# Eurocard_VME_3U.net
KiCad netlist of a schematic drawn in Altium Designer
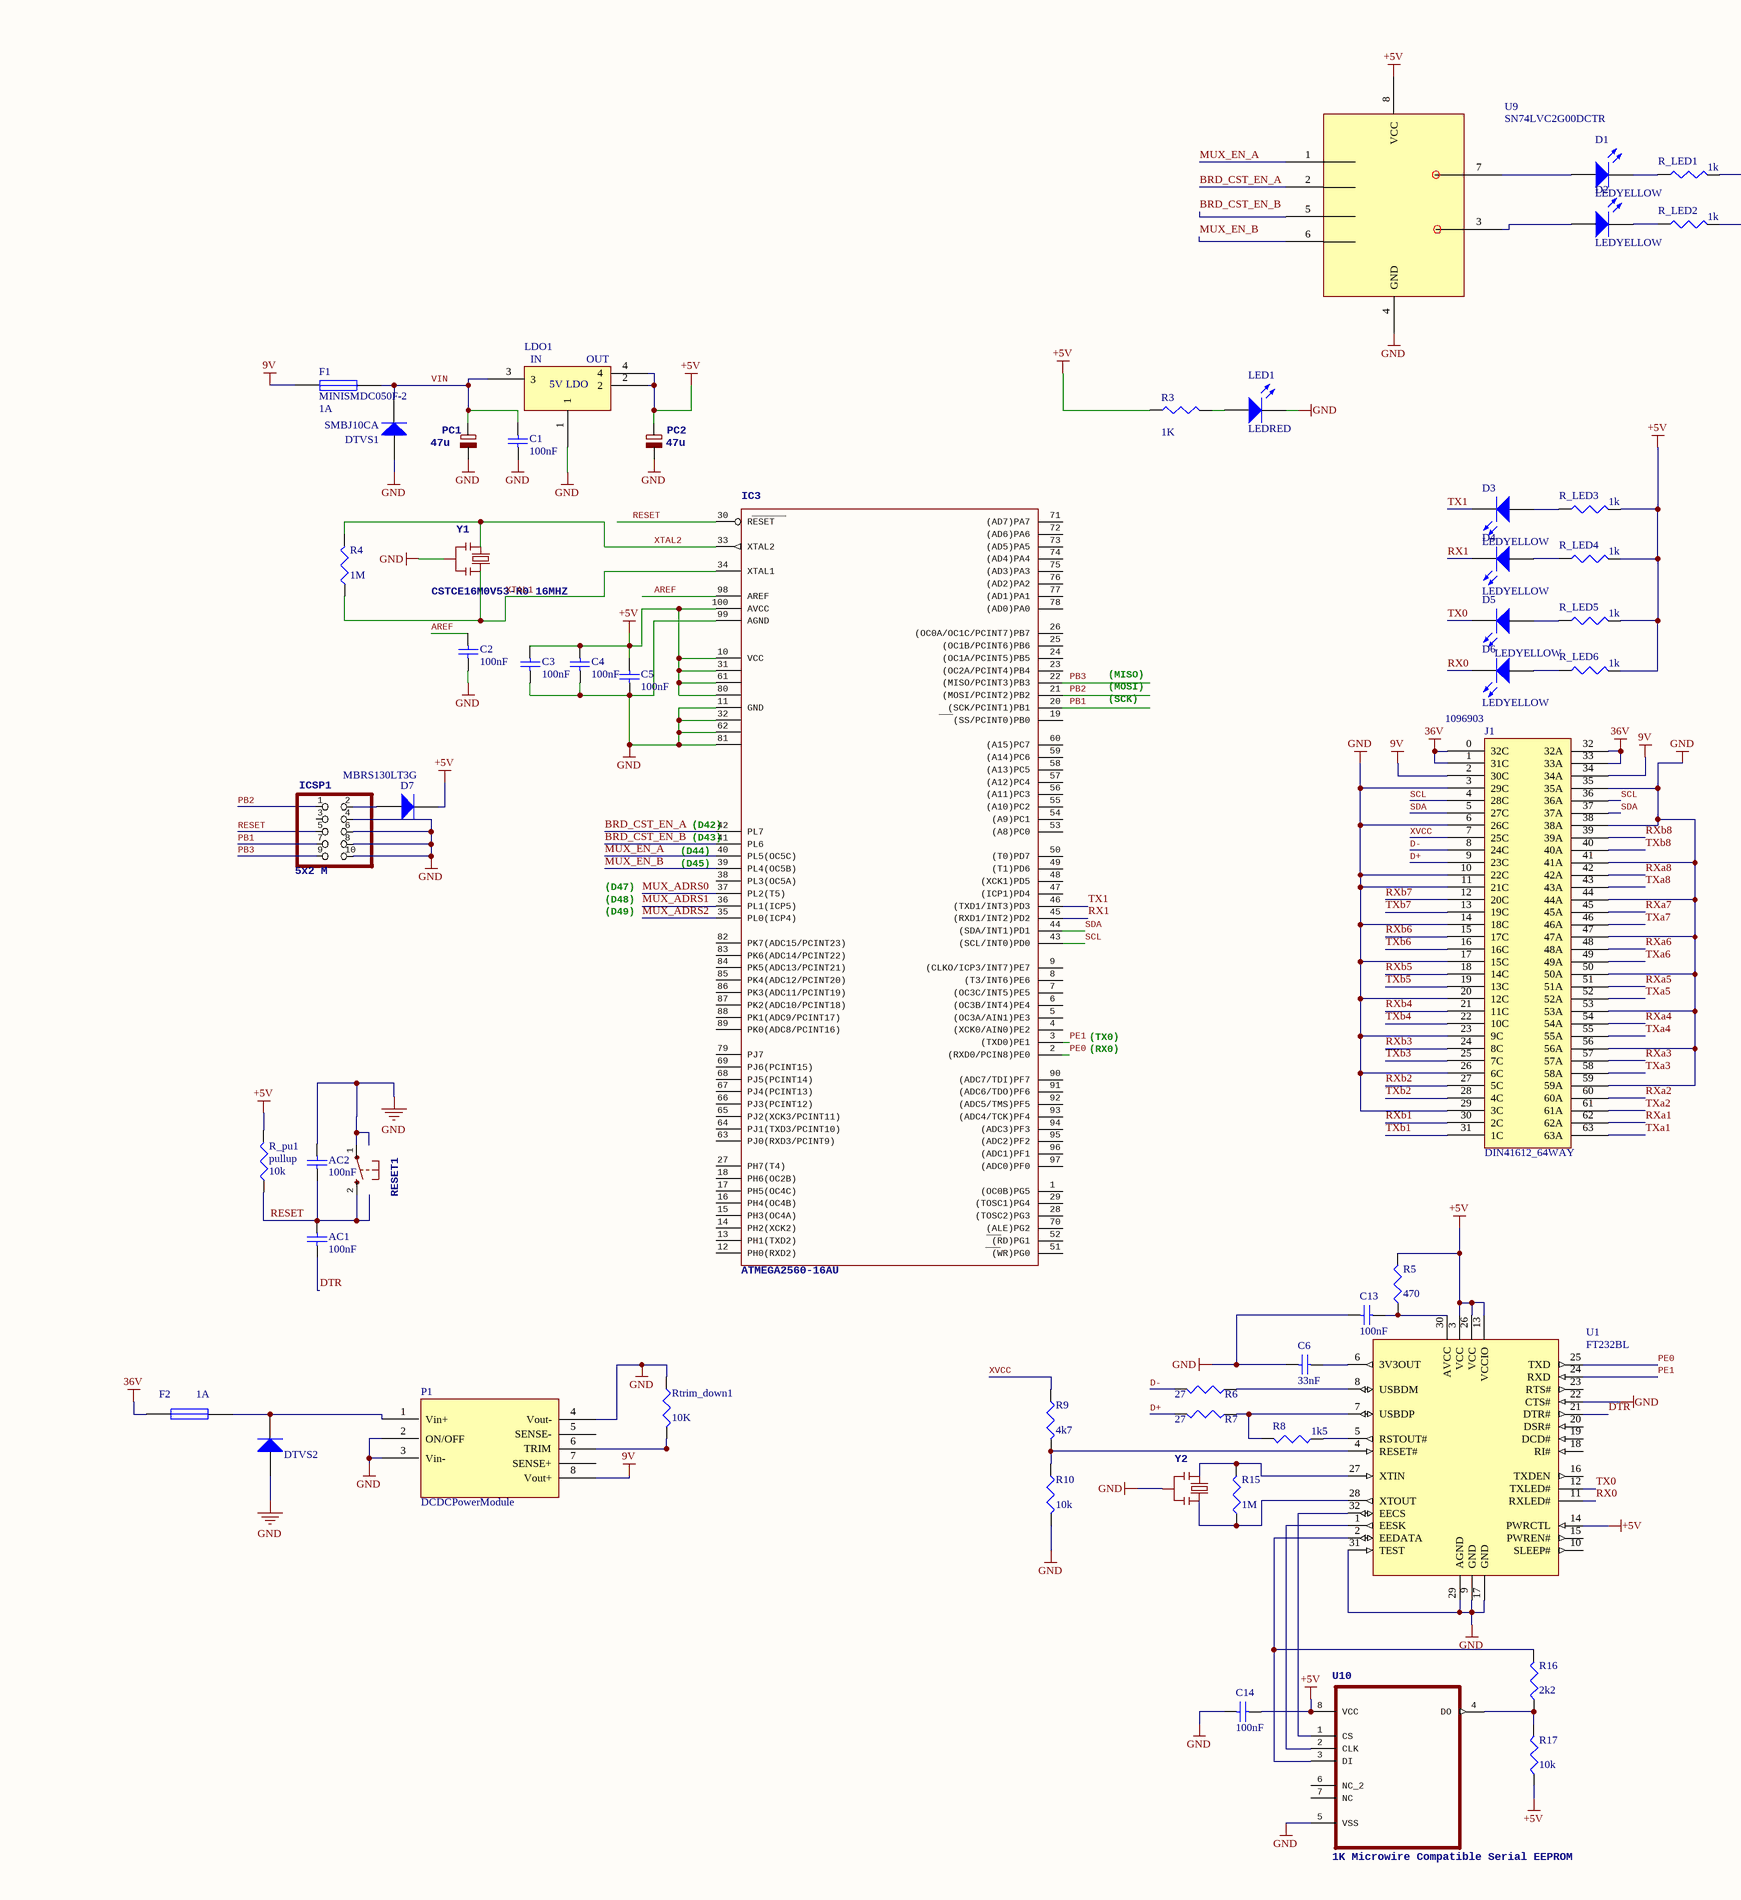
[diagram p0: Eurocard VME 3U (3.937 x 8.660 inches).schdoc, left]
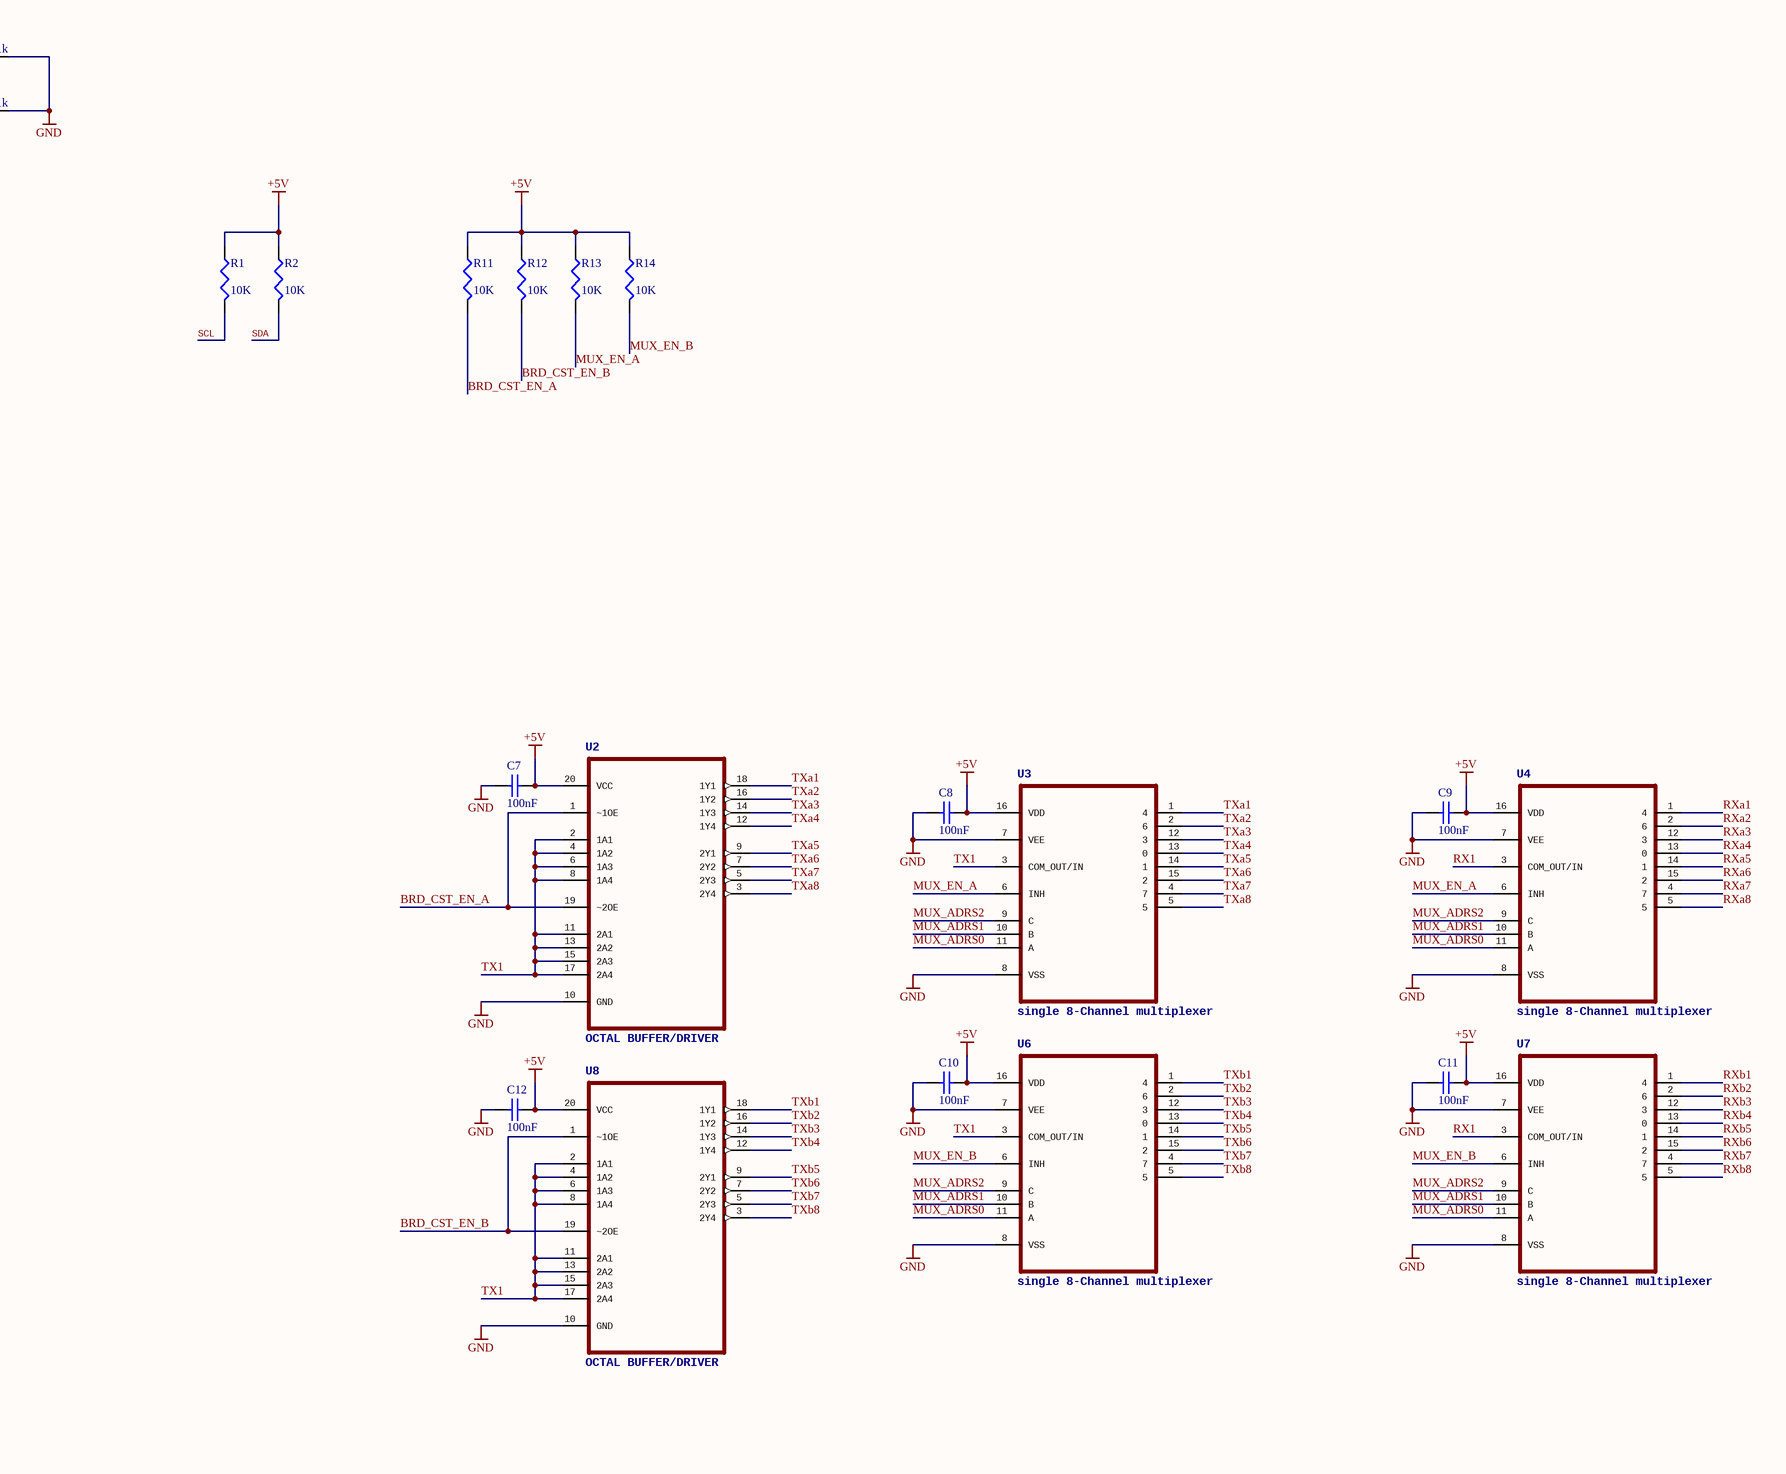
[diagram p1: Eurocard VME 3U (3.937 x 8.660 inches).schdoc, right]

(export (version "E")
  (design (tool "Eeschema 10.0.6"))
  (components
    (comp (ref "AC1")
      (value "100nF")
      (footprint "1608[0603]")
      (description "Capacitor (Semiconductor SIM Model)")
      (fields
        (field (name "PARTNO") "CC0603KRX7R9BB104")
        (field (name "Comment") "Cap Semi")
        (field (name "PUBLISHER") "Altium Limited")
      )
      (libsource (lib "Miscellaneous Devices") (part "Cap Semi"))
    )
    (comp (ref "AC2")
      (value "100nF")
      (footprint "1608[0603]")
      (description "Capacitor (Semiconductor SIM Model)")
      (fields
        (field (name "PARTNO") "CC0603KRX7R9BB104")
        (field (name "Comment") "Cap Semi")
        (field (name "PUBLISHER") "Altium Limited")
      )
      (libsource (lib "Miscellaneous Devices") (part "Cap Semi"))
    )
    (comp (ref "C1")
      (value "100nF")
      (footprint "1608[0603]")
      (description "Capacitor (Semiconductor SIM Model)")
      (fields
        (field (name "PARTNO") "CC0603KRX7R9BB104")
        (field (name "Comment") "Cap Semi")
        (field (name "PUBLISHER") "Altium Limited")
      )
      (libsource (lib "Miscellaneous Devices") (part "Cap Semi"))
    )
    (comp (ref "C2")
      (value "100nF")
      (footprint "1608[0603]")
      (description "Capacitor (Semiconductor SIM Model)")
      (fields
        (field (name "PARTNO") "CC0603KRX7R9BB104")
        (field (name "Comment") "Cap Semi")
        (field (name "PUBLISHER") "Altium Limited")
      )
      (libsource (lib "Miscellaneous Devices") (part "Cap Semi"))
    )
    (comp (ref "C3")
      (value "100nF")
      (footprint "1608[0603]")
      (description "Capacitor (Semiconductor SIM Model)")
      (fields
        (field (name "PARTNO") "CC0603KRX7R9BB104")
        (field (name "Comment") "Cap Semi")
        (field (name "PUBLISHER") "Altium Limited")
      )
      (libsource (lib "Miscellaneous Devices") (part "Cap Semi"))
    )
    (comp (ref "C4")
      (value "100nF")
      (footprint "1608[0603]")
      (description "Capacitor (Semiconductor SIM Model)")
      (fields
        (field (name "PARTNO") "CC0603KRX7R9BB104")
        (field (name "Comment") "Cap Semi")
        (field (name "PUBLISHER") "Altium Limited")
      )
      (libsource (lib "Miscellaneous Devices") (part "Cap Semi"))
    )
    (comp (ref "C5")
      (value "100nF")
      (footprint "1608[0603]")
      (description "Capacitor (Semiconductor SIM Model)")
      (fields
        (field (name "PARTNO") "CC0603KRX7R9BB104")
        (field (name "Comment") "Cap Semi")
        (field (name "PUBLISHER") "Altium Limited")
      )
      (libsource (lib "Miscellaneous Devices") (part "Cap Semi"))
    )
    (comp (ref "C6")
      (value "33nF")
      (footprint "1608[0603]")
      (description "Capacitor (Semiconductor SIM Model)")
      (fields
        (field (name "PARTNO") "0603B332J500CT")
        (field (name "Comment") "Cap Semi")
        (field (name "PUBLISHER") "Altium Limited")
      )
      (libsource (lib "Miscellaneous Devices") (part "Cap Semi"))
    )
    (comp (ref "C7")
      (value "100nF")
      (footprint "1608[0603]")
      (description "Capacitor (Semiconductor SIM Model)")
      (fields (field (name "PARTNO") "CC0603KRX7R9BB104") (field (name "PUBLISHER") "Altium Limited"))
      (libsource (lib "Miscellaneous Devices") (part "Cap Semi"))
    )
    (comp (ref "C8")
      (value "100nF")
      (footprint "1608[0603]")
      (description "Capacitor (Semiconductor SIM Model)")
      (fields (field (name "PARTNO") "CC0603KRX7R9BB104") (field (name "PUBLISHER") "Altium Limited"))
      (libsource (lib "Miscellaneous Devices") (part "Cap Semi"))
    )
    (comp (ref "C9")
      (value "100nF")
      (footprint "1608[0603]")
      (description "Capacitor (Semiconductor SIM Model)")
      (fields (field (name "PARTNO") "CC0603KRX7R9BB104") (field (name "PUBLISHER") "Altium Limited"))
      (libsource (lib "Miscellaneous Devices") (part "Cap Semi"))
    )
    (comp (ref "C10")
      (value "100nF")
      (footprint "1608[0603]")
      (description "Capacitor (Semiconductor SIM Model)")
      (fields (field (name "PARTNO") "CC0603KRX7R9BB104") (field (name "PUBLISHER") "Altium Limited"))
      (libsource (lib "Miscellaneous Devices") (part "Cap Semi"))
    )
    (comp (ref "C11")
      (value "100nF")
      (footprint "1608[0603]")
      (description "Capacitor (Semiconductor SIM Model)")
      (fields (field (name "PARTNO") "CC0603KRX7R9BB104") (field (name "PUBLISHER") "Altium Limited"))
      (libsource (lib "Miscellaneous Devices") (part "Cap Semi"))
    )
    (comp (ref "C12")
      (value "100nF")
      (footprint "1608[0603]")
      (description "Capacitor (Semiconductor SIM Model)")
      (fields (field (name "PARTNO") "CC0603KRX7R9BB104") (field (name "PUBLISHER") "Altium Limited"))
      (libsource (lib "Miscellaneous Devices") (part "Cap Semi"))
    )
    (comp (ref "C13")
      (value "100nF")
      (footprint "1608[0603]")
      (description "Capacitor (Semiconductor SIM Model)")
      (fields
        (field (name "PARTNO") "CC0603KRX7R9BB104")
        (field (name "Comment") "Cap Semi")
        (field (name "PUBLISHER") "Altium Limited")
      )
      (libsource (lib "Miscellaneous Devices") (part "Cap Semi"))
    )
    (comp (ref "C14")
      (value "100nF")
      (footprint "1608[0603]")
      (description "Capacitor (Semiconductor SIM Model)")
      (fields
        (field (name "PARTNO") "CC0603KRX7R9BB104")
        (field (name "Comment") "Cap Semi")
        (field (name "PUBLISHER") "Altium Limited")
      )
      (libsource (lib "Miscellaneous Devices") (part "Cap Semi"))
    )
    (comp (ref "D1")
      (value "LEDYELLOW")
      (footprint "LEDYELLOW")
      (fields (field (name "PARTNO") "550-0307F"))
      (libsource (lib "G2_LV") (part "LEDYELLOW"))
    )
    (comp (ref "D2")
      (value "LEDYELLOW")
      (footprint "LEDYELLOW")
      (fields (field (name "PARTNO") "550-0307F"))
      (libsource (lib "G2_LV") (part "LEDYELLOW"))
    )
    (comp (ref "D3")
      (value "LEDYELLOW")
      (footprint "LEDYELLOW")
      (fields (field (name "PARTNO") "550-0307F"))
      (libsource (lib "G2_LV") (part "LEDYELLOW"))
    )
    (comp (ref "D4")
      (value "LEDYELLOW")
      (footprint "LEDYELLOW")
      (fields (field (name "PARTNO") "550-0307F"))
      (libsource (lib "G2_LV") (part "LEDYELLOW"))
    )
    (comp (ref "D5")
      (value "LEDYELLOW")
      (footprint "LEDYELLOW")
      (fields (field (name "PARTNO") "550-0307F"))
      (libsource (lib "G2_LV") (part "LEDYELLOW"))
    )
    (comp (ref "D6")
      (value "LEDYELLOW")
      (footprint "LEDYELLOW")
      (fields (field (name "PARTNO") "550-0307F"))
      (libsource (lib "G2_LV") (part "LEDYELLOW"))
    )
    (comp (ref "D7")
      (value "MBRS130LT3G")
      (footprint "SMB-403A")
      (description "Power Diode")
      (fields (field (name "PUBLISHER") "Altium Limited"))
      (libsource (lib "G2_LV") (part "MBRS130LT3G"))
    )
    (comp (ref "DTVS1")
      (value "SMBJ10CA")
      (footprint "DO-214AA")
      (description "TVS")
      (fields (field (name "PUBLISHER") "Altium Limited"))
      (libsource (lib "G2_LV") (part "SMBJ"))
    )
    (comp (ref "DTVS2")
      (value "SMBJ48A")
      (footprint "SMBJ")
      (description "TVS")
      (fields (field (name "PARTNO") "SMBJ36A") (field (name "PUBLISHER") "Altium Limited"))
      (libsource (lib "G2_LV") (part "SMBJ"))
    )
    (comp (ref "F1")
      (value "MINISMDC050F-2")
      (footprint "MF-MSMF1")
      (description "Fuse")
      (fields (field (name "TRIPPING CURRENT") "1A") (field (name "PUBLISHER") "Altium Limited"))
      (libsource (lib "G2_LV") (part "Fuse 1"))
    )
    (comp (ref "F2")
      (value "~")
      (footprint "LV1:MC33192")
      (description "Fuse")
      (fields
        (field (name "TRIPPING CURRENT") "1A")
        (field (name "PARTNO") "MC33192")
        (field (name "PUBLISHER") "Altium Limited")
      )
      (libsource (lib "G2_LV") (part "Fuse 1"))
    )
    (comp (ref "IC3")
      (value "ATMEGA2560-16AU")
      (footprint "LV1:100A_N")
      (libsource (lib "SmartPrj") (part "ATMEGA2560AU"))
    )
    (comp (ref "ICSP1")
      (value "5x2 M")
      (footprint "2X05")
      (fields (field (name "PARTNO") "2-1761605-3"))
      (libsource (lib "G2_LV") (part "PINHD-2X5"))
    )
    (comp (ref "J1")
      (value "DIN41612_64WAY")
      (footprint "09 03 164 6919")
      (fields (field (name "PARTNO") "0903 164 6921") (field (name "SUPPLIER PART NUMBER 1") "1096903"))
      (libsource (lib "G2_LV") (part "DIN41612_64WAY"))
    )
    (comp (ref "LDO1")
      (value "LDO_5V")
      (footprint "SOT223")
      (fields (field (name "PARTNO") "NCP1117ST50T3G"))
      (libsource (lib "G2_LV") (part "LDO_5V"))
    )
    (comp (ref "LED1")
      (value "LEDRED")
      (footprint "LEDRED")
      (fields (field (name "PARTNO") "550-0407F"))
      (libsource (lib "G2_LV") (part "LEDRED"))
    )
    (comp (ref "P1")
      (value "DCDCPowerModule")
      (footprint "EHHD006A0B41-HZ")
      (fields (field (name "PARTNO") "EHHD006A0B41-HZ"))
      (libsource (lib "G2_LV") (part "DCDCPowerModule"))
    )
    (comp (ref "PC1")
      (value "47u")
      (footprint "PANASONIC_D")
      (description "POLARIZED CAPACITOR, European symbol")
      (fields (field (name "PARTNO") "EEE1EA470WAP"))
      (libsource (lib "rcl") (part "CPOL-EUD"))
    )
    (comp (ref "PC2")
      (value "47u")
      (footprint "PANASONIC_D")
      (description "POLARIZED CAPACITOR, European symbol")
      (fields (field (name "PARTNO") "EEE1EA470WAP"))
      (libsource (lib "rcl") (part "CPOL-EUD"))
    )
    (comp (ref "R1")
      (value "10K")
      (footprint "J1-0603")
      (description "Resistor")
      (fields (field (name "PUBLISHER") "Altium Limited"))
      (libsource (lib "Miscellaneous Devices") (part "Res3"))
    )
    (comp (ref "R2")
      (value "10K")
      (footprint "J1-0603")
      (description "Resistor")
      (fields (field (name "PUBLISHER") "Altium Limited"))
      (libsource (lib "Miscellaneous Devices") (part "Res3"))
    )
    (comp (ref "R3")
      (value "1K")
      (footprint "J1-0603")
      (description "Resistor")
      (fields (field (name "PUBLISHER") "Altium Limited"))
      (libsource (lib "Miscellaneous Devices") (part "Res3"))
    )
    (comp (ref "R4")
      (value "1M")
      (footprint "J1-0603")
      (description "Resistor")
      (fields (field (name "PUBLISHER") "Altium Limited"))
      (libsource (lib "Miscellaneous Devices") (part "Res3"))
    )
    (comp (ref "R5")
      (value "470")
      (footprint "J1-0603")
      (description "Resistor")
      (fields (field (name "PUBLISHER") "Altium Limited"))
      (libsource (lib "Miscellaneous Devices") (part "Res3"))
    )
    (comp (ref "R6")
      (value "27")
      (footprint "J1-0603")
      (description "Resistor")
      (fields (field (name "PUBLISHER") "Altium Limited"))
      (libsource (lib "Miscellaneous Devices") (part "Res3"))
    )
    (comp (ref "R7")
      (value "27")
      (footprint "J1-0603")
      (description "Resistor")
      (fields (field (name "PUBLISHER") "Altium Limited"))
      (libsource (lib "Miscellaneous Devices") (part "Res3"))
    )
    (comp (ref "R8")
      (value "1k5")
      (footprint "J1-0603")
      (description "Resistor")
      (fields (field (name "PUBLISHER") "Altium Limited"))
      (libsource (lib "Miscellaneous Devices") (part "Res3"))
    )
    (comp (ref "R9")
      (value "4k7")
      (footprint "J1-0603")
      (description "Resistor")
      (fields (field (name "PUBLISHER") "Altium Limited"))
      (libsource (lib "Miscellaneous Devices") (part "Res3"))
    )
    (comp (ref "R10")
      (value "10k")
      (footprint "J1-0603")
      (description "Resistor")
      (fields (field (name "PUBLISHER") "Altium Limited"))
      (libsource (lib "Miscellaneous Devices") (part "Res3"))
    )
    (comp (ref "R11")
      (value "10K")
      (footprint "J1-0603")
      (description "Resistor")
      (fields (field (name "PUBLISHER") "Altium Limited"))
      (libsource (lib "Miscellaneous Devices") (part "Res3"))
    )
    (comp (ref "R12")
      (value "10K")
      (footprint "J1-0603")
      (description "Resistor")
      (fields (field (name "PUBLISHER") "Altium Limited"))
      (libsource (lib "Miscellaneous Devices") (part "Res3"))
    )
    (comp (ref "R13")
      (value "10K")
      (footprint "J1-0603")
      (description "Resistor")
      (fields (field (name "PUBLISHER") "Altium Limited"))
      (libsource (lib "Miscellaneous Devices") (part "Res3"))
    )
    (comp (ref "R14")
      (value "10K")
      (footprint "J1-0603")
      (description "Resistor")
      (fields (field (name "PUBLISHER") "Altium Limited"))
      (libsource (lib "Miscellaneous Devices") (part "Res3"))
    )
    (comp (ref "R15")
      (value "1M")
      (footprint "J1-0603")
      (description "Resistor")
      (fields (field (name "PUBLISHER") "Altium Limited"))
      (libsource (lib "Miscellaneous Devices") (part "Res3"))
    )
    (comp (ref "R16")
      (value "2k2")
      (footprint "J1-0603")
      (description "Resistor")
      (fields (field (name "PUBLISHER") "Altium Limited"))
      (libsource (lib "Miscellaneous Devices") (part "Res3"))
    )
    (comp (ref "R17")
      (value "10k")
      (footprint "J1-0603")
      (description "Resistor")
      (fields (field (name "PUBLISHER") "Altium Limited"))
      (libsource (lib "Miscellaneous Devices") (part "Res3"))
    )
    (comp (ref "RESET1")
      (value "PB_RST")
      (footprint "1-1825027-4")
      (fields (field (name "PARTNO") "1-1825027-4"))
      (libsource (lib "G2_LV") (part "PB_RST"))
    )
    (comp (ref "Rtrim_down1")
      (value "10K")
      (footprint "J1-0603")
      (description "Resistor")
      (fields (field (name "PUBLISHER") "Altium Limited"))
      (libsource (lib "Miscellaneous Devices") (part "Res3"))
    )
    (comp (ref "R_LED1")
      (value "1k")
      (footprint "J1-0603")
      (description "Resistor")
      (fields (field (name "Comment") "Res3") (field (name "PUBLISHER") "Altium Limited"))
      (libsource (lib "Miscellaneous Devices") (part "Res3"))
    )
    (comp (ref "R_LED2")
      (value "1k")
      (footprint "J1-0603")
      (description "Resistor")
      (fields (field (name "Comment") "Res3") (field (name "PUBLISHER") "Altium Limited"))
      (libsource (lib "Miscellaneous Devices") (part "Res3"))
    )
    (comp (ref "R_LED3")
      (value "1k")
      (footprint "J1-0603")
      (description "Resistor")
      (fields (field (name "Comment") "Res3") (field (name "PUBLISHER") "Altium Limited"))
      (libsource (lib "Miscellaneous Devices") (part "Res3"))
    )
    (comp (ref "R_LED4")
      (value "1k")
      (footprint "J1-0603")
      (description "Resistor")
      (fields (field (name "Comment") "Res3") (field (name "PUBLISHER") "Altium Limited"))
      (libsource (lib "Miscellaneous Devices") (part "Res3"))
    )
    (comp (ref "R_LED5")
      (value "1k")
      (footprint "J1-0603")
      (description "Resistor")
      (fields (field (name "Comment") "Res3") (field (name "PUBLISHER") "Altium Limited"))
      (libsource (lib "Miscellaneous Devices") (part "Res3"))
    )
    (comp (ref "R_LED6")
      (value "1k")
      (footprint "J1-0603")
      (description "Resistor")
      (fields (field (name "Comment") "Res3") (field (name "PUBLISHER") "Altium Limited"))
      (libsource (lib "Miscellaneous Devices") (part "Res3"))
    )
    (comp (ref "R_pu1")
      (value "pullup")
      (footprint "J1-0603")
      (description "Resistor")
      (fields (field (name "ALTIUM_VALUE") "10k") (field (name "PUBLISHER") "Altium Limited"))
      (libsource (lib "Miscellaneous Devices") (part "Res3"))
    )
    (comp (ref "U1")
      (value "FT232BL")
      (footprint "LQFP-32_N")
      (description "USB UART Asynchronous Serial Data Transfer Chip, 0 to +70 degC, 32-pin LQFP, Pb-Free")
      (fields (field (name "MANUFACTURER") "FTDI"))
      (libsource (lib "FTDI FT Series") (part "FT232BL"))
    )
    (comp (ref "U2")
      (value "OCTAL BUFFER/DRIVER")
      (footprint "SOP65P640X120-20N")
      (fields (field (name "PARTNO") "SN74LVC244APWR"))
      (libsource (lib "G2_LV") (part "SN74LVC244APWR"))
    )
    (comp (ref "U3")
      (value "single 8-Channel multiplexer")
      (footprint "SOP65P640X120-16N")
      (fields (field (name "PARTNO") "CD4051BPW"))
      (libsource (lib "G2_LV") (part "CD4051BPW"))
    )
    (comp (ref "U4")
      (value "single 8-Channel multiplexer")
      (footprint "SOP65P640X120-16N")
      (fields (field (name "PARTNO") "CD4051BPW"))
      (libsource (lib "G2_LV") (part "CD4051BPW"))
    )
    (comp (ref "U6")
      (value "single 8-Channel multiplexer")
      (footprint "SOP65P640X120-16N")
      (fields (field (name "PARTNO") "CD4051BPW"))
      (libsource (lib "G2_LV") (part "CD4051BPW"))
    )
    (comp (ref "U7")
      (value "single 8-Channel multiplexer")
      (footprint "SOP65P640X120-16N")
      (fields (field (name "PARTNO") "CD4051BPW"))
      (libsource (lib "G2_LV") (part "CD4051BPW"))
    )
    (comp (ref "U8")
      (value "OCTAL BUFFER/DRIVER")
      (footprint "SOP65P640X120-20N")
      (fields (field (name "PARTNO") "SN74LVC244APWR"))
      (libsource (lib "G2_LV") (part "SN74LVC244APWR"))
    )
    (comp (ref "U9")
      (value "SN74LVC2G00DCTR")
      (footprint "SOP8")
      (libsource (lib "G2_LV") (part "SN74LVC2G00DCTR"))
    )
    (comp (ref "U10")
      (value "1K Microwire Compatible Serial EEPROM")
      (footprint "SOIC127P600X175-8N")
      (fields (field (name "PARTNO") "93LC46B-I/SN"))
      (libsource (lib "G2_LV") (part "93LC46B-I/SN"))
    )
    (comp (ref "Y1")
      (value "CSTCE16M0V53-R0 16MHZ")
      (footprint "RESONATOR")
      (fields (field (name "PARTNO") "CSTCE16M0V53-R0"))
      (libsource (lib "SmartPrj") (part "RESONATORMU"))
    )
    (comp (ref "Y2")
      (value "~")
      (footprint "CSTCR6M00G53-R0")
      (fields (field (name "PARTNO") "CSTCR6M00G53-R0"))
      (libsource (lib "SmartPrj") (part "RESONATORMU"))
    )
  )
  (nets
    (net (code "1") (name "+5V") (class "Default")
      (node (ref "C10") (pin "1") (pinfunction "1_1") (pintype "passive"))
      (node (ref "C11") (pin "1") (pinfunction "1_1") (pintype "passive"))
      (node (ref "C12") (pin "1") (pinfunction "1_1") (pintype "passive"))
      (node (ref "C14") (pin "1") (pinfunction "1_1") (pintype "passive"))
      (node (ref "C3") (pin "2") (pinfunction "2_2") (pintype "passive"))
      (node (ref "C4") (pin "2") (pinfunction "2_2") (pintype "passive"))
      (node (ref "C5") (pin "2") (pinfunction "2_2") (pintype "passive"))
      (node (ref "C7") (pin "1") (pinfunction "1_1") (pintype "passive"))
      (node (ref "C8") (pin "1") (pinfunction "1_1") (pintype "passive"))
      (node (ref "C9") (pin "1") (pinfunction "1_1") (pintype "passive"))
      (node (ref "D7") (pin "1") (pinfunction "K_1") (pintype "passive"))
      (node (ref "IC3") (pin "10") (pinfunction "VCC_10") (pintype "power_in"))
      (node (ref "IC3") (pin "100") (pinfunction "AVCC_100") (pintype "power_in"))
      (node (ref "IC3") (pin "31") (pinfunction "VCC1_31") (pintype "power_in"))
      (node (ref "IC3") (pin "61") (pinfunction "VCC2_61") (pintype "power_in"))
      (node (ref "IC3") (pin "80") (pinfunction "VCC3_80") (pintype "power_in"))
      (node (ref "LDO1") (pin "2") (pinfunction "2_2") (pintype "passive"))
      (node (ref "LDO1") (pin "4") (pinfunction "4_4") (pintype "passive"))
      (node (ref "PC2") (pin "+") (pinfunction "+_+") (pintype "passive"))
      (node (ref "R1") (pin "1") (pinfunction "1_1") (pintype "passive"))
      (node (ref "R11") (pin "1") (pinfunction "1_1") (pintype "passive"))
      (node (ref "R12") (pin "1") (pinfunction "1_1") (pintype "passive"))
      (node (ref "R13") (pin "1") (pinfunction "1_1") (pintype "passive"))
      (node (ref "R14") (pin "1") (pinfunction "1_1") (pintype "passive"))
      (node (ref "R17") (pin "1") (pinfunction "1_1") (pintype "passive"))
      (node (ref "R2") (pin "1") (pinfunction "1_1") (pintype "passive"))
      (node (ref "R3") (pin "1") (pinfunction "1_1") (pintype "passive"))
      (node (ref "R5") (pin "2") (pinfunction "2_2") (pintype "passive"))
      (node (ref "R_LED3") (pin "2") (pinfunction "2_2") (pintype "passive"))
      (node (ref "R_LED4") (pin "2") (pinfunction "2_2") (pintype "passive"))
      (node (ref "R_LED5") (pin "2") (pinfunction "2_2") (pintype "passive"))
      (node (ref "R_LED6") (pin "2") (pinfunction "2_2") (pintype "passive"))
      (node (ref "R_pu1") (pin "2") (pinfunction "2_2") (pintype "passive"))
      (node (ref "U1") (pin "13") (pinfunction "VCCIO_13") (pintype "power_in"))
      (node (ref "U1") (pin "14") (pinfunction "PWRCTL_14") (pintype "input"))
      (node (ref "U1") (pin "26") (pinfunction "VCC_26") (pintype "power_in"))
      (node (ref "U1") (pin "3") (pinfunction "VCC_3") (pintype "power_in"))
      (node (ref "U10") (pin "8") (pinfunction "VCC_8") (pintype "power_in"))
      (node (ref "U2") (pin "20") (pinfunction "VCC_20") (pintype "power_in"))
      (node (ref "U3") (pin "16") (pinfunction "VDD_16") (pintype "power_in"))
      (node (ref "U4") (pin "16") (pinfunction "VDD_16") (pintype "power_in"))
      (node (ref "U6") (pin "16") (pinfunction "VDD_16") (pintype "power_in"))
      (node (ref "U7") (pin "16") (pinfunction "VDD_16") (pintype "power_in"))
      (node (ref "U8") (pin "20") (pinfunction "VCC_20") (pintype "power_in"))
      (node (ref "U9") (pin "8") (pinfunction "VCC_8") (pintype "passive"))
    )
    (net (code "2") (name "/AREF") (class "Default")
      (node (ref "C2") (pin "2") (pinfunction "2_2") (pintype "passive"))
      (node (ref "IC3") (pin "98") (pinfunction "AREF_98") (pintype "passive"))
    )
    (net (code "3") (name "/BRD_CST_EN_A") (class "Default")
      (node (ref "IC3") (pin "42") (pinfunction "PL7_42") (pintype "passive"))
      (node (ref "R11") (pin "2") (pinfunction "2_2") (pintype "passive"))
      (node (ref "U2") (pin "1") (pinfunction "~1OE_1") (pintype "passive"))
      (node (ref "U2") (pin "19") (pinfunction "~2OE_19") (pintype "passive"))
      (node (ref "U9") (pin "2") (pinfunction "2_2") (pintype "passive"))
    )
    (net (code "4") (name "/BRD_CST_EN_B") (class "Default")
      (node (ref "IC3") (pin "41") (pinfunction "PL6_41") (pintype "passive"))
      (node (ref "R12") (pin "2") (pinfunction "2_2") (pintype "passive"))
      (node (ref "U8") (pin "1") (pinfunction "~1OE_1") (pintype "passive"))
      (node (ref "U8") (pin "19") (pinfunction "~2OE_19") (pintype "passive"))
      (node (ref "U9") (pin "5") (pinfunction "5_5") (pintype "passive"))
    )
    (net (code "5") (name "/D+") (class "Default")
      (node (ref "J1") (pin "9") (pinfunction "23C_9") (pintype "passive"))
      (node (ref "R7") (pin "2") (pinfunction "2_2") (pintype "passive"))
    )
    (net (code "6") (name "/D-") (class "Default")
      (node (ref "J1") (pin "8") (pinfunction "24C_8") (pintype "passive"))
      (node (ref "R6") (pin "2") (pinfunction "2_2") (pintype "passive"))
    )
    (net (code "7") (name "/DTR") (class "Default")
      (node (ref "AC1") (pin "2") (pinfunction "2_2") (pintype "passive"))
      (node (ref "U1") (pin "21") (pinfunction "DTR#_21") (pintype "output"))
    )
    (net (code "8") (name "/MUX_ADRS0") (class "Default")
      (node (ref "IC3") (pin "37") (pinfunction "PL2(T5)_37") (pintype "passive"))
      (node (ref "U3") (pin "11") (pinfunction "A_11") (pintype "passive"))
      (node (ref "U4") (pin "11") (pinfunction "A_11") (pintype "passive"))
      (node (ref "U6") (pin "11") (pinfunction "A_11") (pintype "passive"))
      (node (ref "U7") (pin "11") (pinfunction "A_11") (pintype "passive"))
    )
    (net (code "9") (name "/MUX_ADRS1") (class "Default")
      (node (ref "IC3") (pin "36") (pinfunction "PL1(ICP5)_36") (pintype "passive"))
      (node (ref "U3") (pin "10") (pinfunction "B_10") (pintype "passive"))
      (node (ref "U4") (pin "10") (pinfunction "B_10") (pintype "passive"))
      (node (ref "U6") (pin "10") (pinfunction "B_10") (pintype "passive"))
      (node (ref "U7") (pin "10") (pinfunction "B_10") (pintype "passive"))
    )
    (net (code "10") (name "/MUX_ADRS2") (class "Default")
      (node (ref "IC3") (pin "35") (pinfunction "PL0(ICP4)_35") (pintype "passive"))
      (node (ref "U3") (pin "9") (pinfunction "C_9") (pintype "passive"))
      (node (ref "U4") (pin "9") (pinfunction "C_9") (pintype "passive"))
      (node (ref "U6") (pin "9") (pinfunction "C_9") (pintype "passive"))
      (node (ref "U7") (pin "9") (pinfunction "C_9") (pintype "passive"))
    )
    (net (code "11") (name "/MUX_EN_A") (class "Default")
      (node (ref "IC3") (pin "40") (pinfunction "PL5(OC5C)_40") (pintype "passive"))
      (node (ref "R13") (pin "2") (pinfunction "2_2") (pintype "passive"))
      (node (ref "U3") (pin "6") (pinfunction "INH_6") (pintype "passive"))
      (node (ref "U4") (pin "6") (pinfunction "INH_6") (pintype "passive"))
      (node (ref "U9") (pin "1") (pinfunction "1_1") (pintype "passive"))
    )
    (net (code "12") (name "/MUX_EN_B") (class "Default")
      (node (ref "IC3") (pin "39") (pinfunction "PL4(OC5B)_39") (pintype "passive"))
      (node (ref "R14") (pin "2") (pinfunction "2_2") (pintype "passive"))
      (node (ref "U6") (pin "6") (pinfunction "INH_6") (pintype "passive"))
      (node (ref "U7") (pin "6") (pinfunction "INH_6") (pintype "passive"))
      (node (ref "U9") (pin "6") (pinfunction "6_6") (pintype "passive"))
    )
    (net (code "13") (name "/PB1") (class "Default")
      (node (ref "IC3") (pin "20") (pinfunction "(SCK/PCINT1)PB1_20") (pintype "passive"))
      (node (ref "ICSP1") (pin "7") (pinfunction "7_7") (pintype "passive"))
    )
    (net (code "14") (name "/PB2") (class "Default")
      (node (ref "IC3") (pin "21") (pinfunction "(MOSI/PCINT2)PB2_21") (pintype "passive"))
      (node (ref "ICSP1") (pin "1") (pinfunction "1_1") (pintype "passive"))
    )
    (net (code "15") (name "/PB3") (class "Default")
      (node (ref "IC3") (pin "22") (pinfunction "(MISO/PCINT3)PB3_22") (pintype "passive"))
      (node (ref "ICSP1") (pin "9") (pinfunction "9_9") (pintype "passive"))
    )
    (net (code "16") (name "/PE0") (class "Default")
      (node (ref "IC3") (pin "2") (pinfunction "(RXD0/PCIN8)PE0_2") (pintype "passive"))
      (node (ref "U1") (pin "25") (pinfunction "TXD_25") (pintype "output"))
    )
    (net (code "17") (name "/PE1") (class "Default")
      (node (ref "IC3") (pin "3") (pinfunction "(TXD0)PE1_3") (pintype "passive"))
      (node (ref "U1") (pin "24") (pinfunction "RXD_24") (pintype "input"))
    )
    (net (code "18") (name "/RESET") (class "Default")
      (node (ref "AC1") (pin "1") (pinfunction "1_1") (pintype "passive"))
      (node (ref "AC2") (pin "1") (pinfunction "1_1") (pintype "passive"))
      (node (ref "IC3") (pin "30") (pinfunction "RESET_30") (pintype "passive"))
      (node (ref "ICSP1") (pin "5") (pinfunction "5_5") (pintype "passive"))
      (node (ref "RESET1") (pin "2") (pinfunction "2_2") (pintype "passive"))
      (node (ref "R_pu1") (pin "1") (pinfunction "1_1") (pintype "passive"))
    )
    (net (code "19") (name "/RX0") (class "Default")
      (node (ref "D6") (pin "1") (pinfunction "K_1") (pintype "passive"))
      (node (ref "U1") (pin "11") (pinfunction "RXLED#_11") (pintype "open_collector"))
    )
    (net (code "20") (name "/RX1") (class "Default")
      (node (ref "D4") (pin "1") (pinfunction "K_1") (pintype "passive"))
      (node (ref "IC3") (pin "45") (pinfunction "(RXD1/INT2)PD2_45") (pintype "passive"))
      (node (ref "U4") (pin "3") (pinfunction "COM_OUT/IN_3") (pintype "passive"))
      (node (ref "U7") (pin "3") (pinfunction "COM_OUT/IN_3") (pintype "passive"))
    )
    (net (code "21") (name "/RXa1") (class "Default")
      (node (ref "J1") (pin "62") (pinfunction "62A_62") (pintype "passive"))
      (node (ref "U4") (pin "1") (pinfunction "4_1") (pintype "passive"))
    )
    (net (code "22") (name "/RXa2") (class "Default")
      (node (ref "J1") (pin "60") (pinfunction "60A_60") (pintype "passive"))
      (node (ref "U4") (pin "2") (pinfunction "6_2") (pintype "passive"))
    )
    (net (code "23") (name "/RXa3") (class "Default")
      (node (ref "J1") (pin "57") (pinfunction "57A_57") (pintype "passive"))
      (node (ref "U4") (pin "12") (pinfunction "3_12") (pintype "passive"))
    )
    (net (code "24") (name "/RXa4") (class "Default")
      (node (ref "J1") (pin "54") (pinfunction "54A_54") (pintype "passive"))
      (node (ref "U4") (pin "13") (pinfunction "0_13") (pintype "passive"))
    )
    (net (code "25") (name "/RXa5") (class "Default")
      (node (ref "J1") (pin "51") (pinfunction "51A_51") (pintype "passive"))
      (node (ref "U4") (pin "14") (pinfunction "1_14") (pintype "passive"))
    )
    (net (code "26") (name "/RXa6") (class "Default")
      (node (ref "J1") (pin "48") (pinfunction "48A_48") (pintype "passive"))
      (node (ref "U4") (pin "15") (pinfunction "2_15") (pintype "passive"))
    )
    (net (code "27") (name "/RXa7") (class "Default")
      (node (ref "J1") (pin "45") (pinfunction "45A_45") (pintype "passive"))
      (node (ref "U4") (pin "4") (pinfunction "7_4") (pintype "passive"))
    )
    (net (code "28") (name "/RXa8") (class "Default")
      (node (ref "J1") (pin "42") (pinfunction "42A_42") (pintype "passive"))
      (node (ref "U4") (pin "5") (pinfunction "5_5") (pintype "passive"))
    )
    (net (code "29") (name "/RXb1") (class "Default")
      (node (ref "J1") (pin "30") (pinfunction "2C_30") (pintype "passive"))
      (node (ref "U7") (pin "1") (pinfunction "4_1") (pintype "passive"))
    )
    (net (code "30") (name "/RXb2") (class "Default")
      (node (ref "J1") (pin "27") (pinfunction "5C_27") (pintype "passive"))
      (node (ref "U7") (pin "2") (pinfunction "6_2") (pintype "passive"))
    )
    (net (code "31") (name "/RXb3") (class "Default")
      (node (ref "J1") (pin "24") (pinfunction "8C_24") (pintype "passive"))
      (node (ref "U7") (pin "12") (pinfunction "3_12") (pintype "passive"))
    )
    (net (code "32") (name "/RXb4") (class "Default")
      (node (ref "J1") (pin "21") (pinfunction "11C_21") (pintype "passive"))
      (node (ref "U7") (pin "13") (pinfunction "0_13") (pintype "passive"))
    )
    (net (code "33") (name "/RXb5") (class "Default")
      (node (ref "J1") (pin "18") (pinfunction "14C_18") (pintype "passive"))
      (node (ref "U7") (pin "14") (pinfunction "1_14") (pintype "passive"))
    )
    (net (code "34") (name "/RXb6") (class "Default")
      (node (ref "J1") (pin "15") (pinfunction "17C_15") (pintype "passive"))
      (node (ref "U7") (pin "15") (pinfunction "2_15") (pintype "passive"))
    )
    (net (code "35") (name "/RXb7") (class "Default")
      (node (ref "J1") (pin "12") (pinfunction "20C_12") (pintype "passive"))
      (node (ref "U7") (pin "4") (pinfunction "7_4") (pintype "passive"))
    )
    (net (code "36") (name "/RXb8") (class "Default")
      (node (ref "J1") (pin "39") (pinfunction "39A_39") (pintype "passive"))
      (node (ref "U7") (pin "5") (pinfunction "5_5") (pintype "passive"))
    )
    (net (code "37") (name "/SCL") (class "Default")
      (node (ref "IC3") (pin "43") (pinfunction "(SCL/INT0)PD0_43") (pintype "passive"))
      (node (ref "J1") (pin "36") (pinfunction "36A_36") (pintype "passive"))
      (node (ref "J1") (pin "4") (pinfunction "28C_4") (pintype "passive"))
      (node (ref "R1") (pin "2") (pinfunction "2_2") (pintype "passive"))
    )
    (net (code "38") (name "/SDA") (class "Default")
      (node (ref "IC3") (pin "44") (pinfunction "(SDA/INT1)PD1_44") (pintype "passive"))
      (node (ref "J1") (pin "37") (pinfunction "37A_37") (pintype "passive"))
      (node (ref "J1") (pin "5") (pinfunction "27C_5") (pintype "passive"))
      (node (ref "R2") (pin "2") (pinfunction "2_2") (pintype "passive"))
    )
    (net (code "39") (name "/TX0") (class "Default")
      (node (ref "D5") (pin "1") (pinfunction "K_1") (pintype "passive"))
      (node (ref "U1") (pin "12") (pinfunction "TXLED#_12") (pintype "open_collector"))
    )
    (net (code "40") (name "/TX1") (class "Default")
      (node (ref "D3") (pin "1") (pinfunction "K_1") (pintype "passive"))
      (node (ref "IC3") (pin "46") (pinfunction "(TXD1/INT3)PD3_46") (pintype "passive"))
      (node (ref "U2") (pin "11") (pinfunction "2A1_11") (pintype "passive"))
      (node (ref "U2") (pin "13") (pinfunction "2A2_13") (pintype "passive"))
      (node (ref "U2") (pin "15") (pinfunction "2A3_15") (pintype "passive"))
      (node (ref "U2") (pin "17") (pinfunction "2A4_17") (pintype "passive"))
      (node (ref "U2") (pin "2") (pinfunction "1A1_2") (pintype "passive"))
      (node (ref "U2") (pin "4") (pinfunction "1A2_4") (pintype "passive"))
      (node (ref "U2") (pin "6") (pinfunction "1A3_6") (pintype "passive"))
      (node (ref "U2") (pin "8") (pinfunction "1A4_8") (pintype "passive"))
      (node (ref "U3") (pin "3") (pinfunction "COM_OUT/IN_3") (pintype "passive"))
      (node (ref "U6") (pin "3") (pinfunction "COM_OUT/IN_3") (pintype "passive"))
      (node (ref "U8") (pin "11") (pinfunction "2A1_11") (pintype "passive"))
      (node (ref "U8") (pin "13") (pinfunction "2A2_13") (pintype "passive"))
      (node (ref "U8") (pin "15") (pinfunction "2A3_15") (pintype "passive"))
      (node (ref "U8") (pin "17") (pinfunction "2A4_17") (pintype "passive"))
      (node (ref "U8") (pin "2") (pinfunction "1A1_2") (pintype "passive"))
      (node (ref "U8") (pin "4") (pinfunction "1A2_4") (pintype "passive"))
      (node (ref "U8") (pin "6") (pinfunction "1A3_6") (pintype "passive"))
      (node (ref "U8") (pin "8") (pinfunction "1A4_8") (pintype "passive"))
    )
    (net (code "41") (name "/TXa1") (class "Default")
      (node (ref "J1") (pin "63") (pinfunction "63A_63") (pintype "passive"))
      (node (ref "U2") (pin "18") (pinfunction "1Y1_18") (pintype "output"))
      (node (ref "U3") (pin "1") (pinfunction "4_1") (pintype "passive"))
    )
    (net (code "42") (name "/TXa2") (class "Default")
      (node (ref "J1") (pin "61") (pinfunction "61A_61") (pintype "passive"))
      (node (ref "U2") (pin "16") (pinfunction "1Y2_16") (pintype "output"))
      (node (ref "U3") (pin "2") (pinfunction "6_2") (pintype "passive"))
    )
    (net (code "43") (name "/TXa3") (class "Default")
      (node (ref "J1") (pin "58") (pinfunction "58A_58") (pintype "passive"))
      (node (ref "U2") (pin "14") (pinfunction "1Y3_14") (pintype "output"))
      (node (ref "U3") (pin "12") (pinfunction "3_12") (pintype "passive"))
    )
    (net (code "44") (name "/TXa4") (class "Default")
      (node (ref "J1") (pin "55") (pinfunction "55A_55") (pintype "passive"))
      (node (ref "U2") (pin "12") (pinfunction "1Y4_12") (pintype "output"))
      (node (ref "U3") (pin "13") (pinfunction "0_13") (pintype "passive"))
    )
    (net (code "45") (name "/TXa5") (class "Default")
      (node (ref "J1") (pin "52") (pinfunction "52A_52") (pintype "passive"))
      (node (ref "U2") (pin "9") (pinfunction "2Y1_9") (pintype "output"))
      (node (ref "U3") (pin "14") (pinfunction "1_14") (pintype "passive"))
    )
    (net (code "46") (name "/TXa6") (class "Default")
      (node (ref "J1") (pin "49") (pinfunction "49A_49") (pintype "passive"))
      (node (ref "U2") (pin "7") (pinfunction "2Y2_7") (pintype "output"))
      (node (ref "U3") (pin "15") (pinfunction "2_15") (pintype "passive"))
    )
    (net (code "47") (name "/TXa7") (class "Default")
      (node (ref "J1") (pin "46") (pinfunction "46A_46") (pintype "passive"))
      (node (ref "U2") (pin "5") (pinfunction "2Y3_5") (pintype "output"))
      (node (ref "U3") (pin "4") (pinfunction "7_4") (pintype "passive"))
    )
    (net (code "48") (name "/TXa8") (class "Default")
      (node (ref "J1") (pin "43") (pinfunction "43A_43") (pintype "passive"))
      (node (ref "U2") (pin "3") (pinfunction "2Y4_3") (pintype "output"))
      (node (ref "U3") (pin "5") (pinfunction "5_5") (pintype "passive"))
    )
    (net (code "49") (name "/TXb1") (class "Default")
      (node (ref "J1") (pin "31") (pinfunction "1C_31") (pintype "passive"))
      (node (ref "U6") (pin "1") (pinfunction "4_1") (pintype "passive"))
      (node (ref "U8") (pin "18") (pinfunction "1Y1_18") (pintype "output"))
    )
    (net (code "50") (name "/TXb2") (class "Default")
      (node (ref "J1") (pin "28") (pinfunction "4C_28") (pintype "passive"))
      (node (ref "U6") (pin "2") (pinfunction "6_2") (pintype "passive"))
      (node (ref "U8") (pin "16") (pinfunction "1Y2_16") (pintype "output"))
    )
    (net (code "51") (name "/TXb3") (class "Default")
      (node (ref "J1") (pin "25") (pinfunction "7C_25") (pintype "passive"))
      (node (ref "U6") (pin "12") (pinfunction "3_12") (pintype "passive"))
      (node (ref "U8") (pin "14") (pinfunction "1Y3_14") (pintype "output"))
    )
    (net (code "52") (name "/TXb4") (class "Default")
      (node (ref "J1") (pin "22") (pinfunction "10C_22") (pintype "passive"))
      (node (ref "U6") (pin "13") (pinfunction "0_13") (pintype "passive"))
      (node (ref "U8") (pin "12") (pinfunction "1Y4_12") (pintype "output"))
    )
    (net (code "53") (name "/TXb5") (class "Default")
      (node (ref "J1") (pin "19") (pinfunction "13C_19") (pintype "passive"))
      (node (ref "U6") (pin "14") (pinfunction "1_14") (pintype "passive"))
      (node (ref "U8") (pin "9") (pinfunction "2Y1_9") (pintype "output"))
    )
    (net (code "54") (name "/TXb6") (class "Default")
      (node (ref "J1") (pin "16") (pinfunction "16C_16") (pintype "passive"))
      (node (ref "U6") (pin "15") (pinfunction "2_15") (pintype "passive"))
      (node (ref "U8") (pin "7") (pinfunction "2Y2_7") (pintype "output"))
    )
    (net (code "55") (name "/TXb7") (class "Default")
      (node (ref "J1") (pin "13") (pinfunction "19C_13") (pintype "passive"))
      (node (ref "U6") (pin "4") (pinfunction "7_4") (pintype "passive"))
      (node (ref "U8") (pin "5") (pinfunction "2Y3_5") (pintype "output"))
    )
    (net (code "56") (name "/TXb8") (class "Default")
      (node (ref "J1") (pin "40") (pinfunction "40A_40") (pintype "passive"))
      (node (ref "U6") (pin "5") (pinfunction "5_5") (pintype "passive"))
      (node (ref "U8") (pin "3") (pinfunction "2Y4_3") (pintype "output"))
    )
    (net (code "57") (name "/VIN") (class "Default")
      (node (ref "C1") (pin "2") (pinfunction "2_2") (pintype "passive"))
      (node (ref "DTVS1") (pin "1") (pinfunction "K_1") (pintype "passive"))
      (node (ref "F1") (pin "2") (pinfunction "2_2") (pintype "passive"))
      (node (ref "LDO1") (pin "3") (pinfunction "3_3") (pintype "passive"))
      (node (ref "PC1") (pin "+") (pinfunction "+_+") (pintype "passive"))
    )
    (net (code "58") (name "/XTAL1") (class "Default")
      (node (ref "IC3") (pin "34") (pinfunction "XTAL1_34") (pintype "passive"))
      (node (ref "R4") (pin "1") (pinfunction "1_1") (pintype "passive"))
      (node (ref "Y1") (pin "3") (pinfunction "3_3") (pintype "passive"))
    )
    (net (code "59") (name "/XTAL2") (class "Default")
      (node (ref "IC3") (pin "33") (pinfunction "XTAL2_33") (pintype "output"))
      (node (ref "R4") (pin "2") (pinfunction "2_2") (pintype "passive"))
      (node (ref "Y1") (pin "1") (pinfunction "1_1") (pintype "passive"))
    )
    (net (code "60") (name "/XVCC") (class "Default")
      (node (ref "J1") (pin "7") (pinfunction "25C_7") (pintype "passive"))
      (node (ref "R9") (pin "1") (pinfunction "1_1") (pintype "passive"))
    )
    (net (code "61") (name "9V") (class "Default")
      (node (ref "F1") (pin "1") (pinfunction "1_1") (pintype "passive"))
      (node (ref "J1") (pin "2") (pinfunction "30C_2") (pintype "passive"))
      (node (ref "J1") (pin "34") (pinfunction "34A_34") (pintype "passive"))
      (node (ref "P1") (pin "8") (pinfunction "Vout+_8") (pintype "passive"))
    )
    (net (code "62") (name "36V") (class "Default")
      (node (ref "F2") (pin "2") (pinfunction "2_2") (pintype "passive"))
      (node (ref "J1") (pin "0") (pinfunction "32C_0") (pintype "passive"))
      (node (ref "J1") (pin "1") (pinfunction "31C_1") (pintype "passive"))
      (node (ref "J1") (pin "32") (pinfunction "32A_32") (pintype "passive"))
      (node (ref "J1") (pin "33") (pinfunction "33A_33") (pintype "passive"))
    )
    (net (code "63") (name "GND") (class "Default")
      (node (ref "AC2") (pin "2") (pinfunction "2_2") (pintype "passive"))
      (node (ref "C1") (pin "1") (pinfunction "1_1") (pintype "passive"))
      (node (ref "C10") (pin "2") (pinfunction "2_2") (pintype "passive"))
      (node (ref "C11") (pin "2") (pinfunction "2_2") (pintype "passive"))
      (node (ref "C12") (pin "2") (pinfunction "2_2") (pintype "passive"))
      (node (ref "C13") (pin "2") (pinfunction "2_2") (pintype "passive"))
      (node (ref "C14") (pin "2") (pinfunction "2_2") (pintype "passive"))
      (node (ref "C2") (pin "1") (pinfunction "1_1") (pintype "passive"))
      (node (ref "C3") (pin "1") (pinfunction "1_1") (pintype "passive"))
      (node (ref "C4") (pin "1") (pinfunction "1_1") (pintype "passive"))
      (node (ref "C5") (pin "1") (pinfunction "1_1") (pintype "passive"))
      (node (ref "C6") (pin "2") (pinfunction "2_2") (pintype "passive"))
      (node (ref "C7") (pin "2") (pinfunction "2_2") (pintype "passive"))
      (node (ref "C8") (pin "2") (pinfunction "2_2") (pintype "passive"))
      (node (ref "C9") (pin "2") (pinfunction "2_2") (pintype "passive"))
      (node (ref "DTVS1") (pin "2") (pinfunction "A_2") (pintype "passive"))
      (node (ref "DTVS2") (pin "2") (pinfunction "A_2") (pintype "passive"))
      (node (ref "IC3") (pin "11") (pinfunction "GND_11") (pintype "power_in"))
      (node (ref "IC3") (pin "32") (pinfunction "GND1_32") (pintype "power_in"))
      (node (ref "IC3") (pin "62") (pinfunction "GND2_62") (pintype "power_in"))
      (node (ref "IC3") (pin "81") (pinfunction "GND3_81") (pintype "power_in"))
      (node (ref "IC3") (pin "99") (pinfunction "AGND_99") (pintype "power_in"))
      (node (ref "ICSP1") (pin "10") (pinfunction "10_10") (pintype "passive"))
      (node (ref "ICSP1") (pin "4") (pinfunction "4_4") (pintype "passive"))
      (node (ref "ICSP1") (pin "6") (pinfunction "6_6") (pintype "passive"))
      (node (ref "ICSP1") (pin "8") (pinfunction "8_8") (pintype "passive"))
      (node (ref "J1") (pin "10") (pinfunction "22C_10") (pintype "passive"))
      (node (ref "J1") (pin "11") (pinfunction "21C_11") (pintype "passive"))
      (node (ref "J1") (pin "14") (pinfunction "18C_14") (pintype "passive"))
      (node (ref "J1") (pin "17") (pinfunction "15C_17") (pintype "passive"))
      (node (ref "J1") (pin "20") (pinfunction "12C_20") (pintype "passive"))
      (node (ref "J1") (pin "23") (pinfunction "9C_23") (pintype "passive"))
      (node (ref "J1") (pin "26") (pinfunction "6C_26") (pintype "passive"))
      (node (ref "J1") (pin "29") (pinfunction "3C_29") (pintype "passive"))
      (node (ref "J1") (pin "3") (pinfunction "29C_3") (pintype "passive"))
      (node (ref "J1") (pin "35") (pinfunction "35A_35") (pintype "passive"))
      (node (ref "J1") (pin "38") (pinfunction "38A_38") (pintype "passive"))
      (node (ref "J1") (pin "41") (pinfunction "41A_41") (pintype "passive"))
      (node (ref "J1") (pin "44") (pinfunction "44A_44") (pintype "passive"))
      (node (ref "J1") (pin "47") (pinfunction "47A_47") (pintype "passive"))
      (node (ref "J1") (pin "50") (pinfunction "50A_50") (pintype "passive"))
      (node (ref "J1") (pin "53") (pinfunction "53A_53") (pintype "passive"))
      (node (ref "J1") (pin "56") (pinfunction "56A_56") (pintype "passive"))
      (node (ref "J1") (pin "59") (pinfunction "59A_59") (pintype "passive"))
      (node (ref "J1") (pin "6") (pinfunction "26C_6") (pintype "passive"))
      (node (ref "LDO1") (pin "1") (pinfunction "1_1") (pintype "passive"))
      (node (ref "LED1") (pin "1") (pinfunction "K_1") (pintype "passive"))
      (node (ref "P1") (pin "2") (pinfunction "ON/OFF_2") (pintype "passive"))
      (node (ref "P1") (pin "3") (pinfunction "Vin-_3") (pintype "passive"))
      (node (ref "P1") (pin "4") (pinfunction "Vout-_4") (pintype "passive"))
      (node (ref "PC1") (pin "-") (pinfunction "-_-") (pintype "passive"))
      (node (ref "PC2") (pin "-") (pinfunction "-_-") (pintype "passive"))
      (node (ref "R10") (pin "2") (pinfunction "2_2") (pintype "passive"))
      (node (ref "RESET1") (pin "1") (pinfunction "1_1") (pintype "passive"))
      (node (ref "R_LED1") (pin "2") (pinfunction "2_2") (pintype "passive"))
      (node (ref "R_LED2") (pin "2") (pinfunction "2_2") (pintype "passive"))
      (node (ref "Rtrim_down1") (pin "1") (pinfunction "1_1") (pintype "passive"))
      (node (ref "U1") (pin "17") (pinfunction "GND_17") (pintype "power_in"))
      (node (ref "U1") (pin "22") (pinfunction "CTS#_22") (pintype "input"))
      (node (ref "U1") (pin "29") (pinfunction "AGND_29") (pintype "power_in"))
      (node (ref "U1") (pin "31") (pinfunction "TEST_31") (pintype "input"))
      (node (ref "U1") (pin "9") (pinfunction "GND_9") (pintype "power_in"))
      (node (ref "U10") (pin "5") (pinfunction "VSS_5") (pintype "passive"))
      (node (ref "U2") (pin "10") (pinfunction "GND_10") (pintype "passive"))
      (node (ref "U3") (pin "7") (pinfunction "VEE_7") (pintype "power_in"))
      (node (ref "U3") (pin "8") (pinfunction "VSS_8") (pintype "power_in"))
      (node (ref "U4") (pin "7") (pinfunction "VEE_7") (pintype "power_in"))
      (node (ref "U4") (pin "8") (pinfunction "VSS_8") (pintype "power_in"))
      (node (ref "U6") (pin "7") (pinfunction "VEE_7") (pintype "power_in"))
      (node (ref "U6") (pin "8") (pinfunction "VSS_8") (pintype "power_in"))
      (node (ref "U7") (pin "7") (pinfunction "VEE_7") (pintype "power_in"))
      (node (ref "U7") (pin "8") (pinfunction "VSS_8") (pintype "power_in"))
      (node (ref "U8") (pin "10") (pinfunction "GND_10") (pintype "passive"))
      (node (ref "U9") (pin "4") (pinfunction "GND_4") (pintype "passive"))
      (node (ref "Y1") (pin "2") (pinfunction "2_2") (pintype "passive"))
      (node (ref "Y2") (pin "2") (pinfunction "2_2") (pintype "passive"))
    )
    (net (code "64") (name "Net-(D1-A)") (class "Default")
      (node (ref "D1") (pin "2") (pinfunction "A_2") (pintype "passive"))
      (node (ref "U9") (pin "7") (pinfunction "7_7") (pintype "passive"))
    )
    (net (code "65") (name "Net-(D1-K)") (class "Default")
      (node (ref "D1") (pin "1") (pinfunction "K_1") (pintype "passive"))
      (node (ref "R_LED1") (pin "1") (pinfunction "1_1") (pintype "passive"))
    )
    (net (code "66") (name "Net-(D2-A)") (class "Default")
      (node (ref "D2") (pin "2") (pinfunction "A_2") (pintype "passive"))
      (node (ref "U9") (pin "3") (pinfunction "3_3") (pintype "passive"))
    )
    (net (code "67") (name "Net-(D2-K)") (class "Default")
      (node (ref "D2") (pin "1") (pinfunction "K_1") (pintype "passive"))
      (node (ref "R_LED2") (pin "1") (pinfunction "1_1") (pintype "passive"))
    )
    (net (code "68") (name "Net-(D3-A)") (class "Default")
      (node (ref "D3") (pin "2") (pinfunction "A_2") (pintype "passive"))
      (node (ref "R_LED3") (pin "1") (pinfunction "1_1") (pintype "passive"))
    )
    (net (code "69") (name "Net-(D4-A)") (class "Default")
      (node (ref "D4") (pin "2") (pinfunction "A_2") (pintype "passive"))
      (node (ref "R_LED4") (pin "1") (pinfunction "1_1") (pintype "passive"))
    )
    (net (code "70") (name "Net-(D5-A)") (class "Default")
      (node (ref "D5") (pin "2") (pinfunction "A_2") (pintype "passive"))
      (node (ref "R_LED5") (pin "1") (pinfunction "1_1") (pintype "passive"))
    )
    (net (code "71") (name "Net-(D6-A)") (class "Default")
      (node (ref "D6") (pin "2") (pinfunction "A_2") (pintype "passive"))
      (node (ref "R_LED6") (pin "1") (pinfunction "1_1") (pintype "passive"))
    )
    (net (code "72") (name "Net-(D7-A)") (class "Default")
      (node (ref "D7") (pin "2") (pinfunction "A_2") (pintype "passive"))
      (node (ref "ICSP1") (pin "2") (pinfunction "2_2") (pintype "passive"))
    )
    (net (code "73") (name "Net-(DTVS2-K)") (class "Default")
      (node (ref "DTVS2") (pin "1") (pinfunction "K_1") (pintype "passive"))
      (node (ref "F2") (pin "1") (pinfunction "1_1") (pintype "passive"))
      (node (ref "P1") (pin "1") (pinfunction "Vin+_1") (pintype "passive"))
    )
    (net (code "74") (name "Net-(LED1-A)") (class "Default")
      (node (ref "LED1") (pin "2") (pinfunction "A_2") (pintype "passive"))
      (node (ref "R3") (pin "2") (pinfunction "2_2") (pintype "passive"))
    )
    (net (code "75") (name "Net-(P1-TRIM)") (class "Default")
      (node (ref "P1") (pin "6") (pinfunction "TRIM_6") (pintype "passive"))
      (node (ref "Rtrim_down1") (pin "2") (pinfunction "2_2") (pintype "passive"))
    )
    (net (code "76") (name "Net-(U1-3V3OUT)") (class "Default")
      (node (ref "C6") (pin "1") (pinfunction "1_1") (pintype "passive"))
      (node (ref "U1") (pin "6") (pinfunction "3V3OUT_6") (pintype "output"))
    )
    (net (code "77") (name "Net-(U1-AVCC)") (class "Default")
      (node (ref "C13") (pin "1") (pinfunction "1_1") (pintype "passive"))
      (node (ref "R5") (pin "1") (pinfunction "1_1") (pintype "passive"))
      (node (ref "U1") (pin "30") (pinfunction "AVCC_30") (pintype "power_in"))
    )
    (net (code "78") (name "Net-(U1-EECS)") (class "Default")
      (node (ref "U1") (pin "32") (pinfunction "EECS_32") (pintype "bidirectional"))
      (node (ref "U10") (pin "1") (pinfunction "CS_1") (pintype "passive"))
    )
    (net (code "79") (name "Net-(U1-EEDATA)") (class "Default")
      (node (ref "R16") (pin "2") (pinfunction "2_2") (pintype "passive"))
      (node (ref "U1") (pin "2") (pinfunction "EEDATA_2") (pintype "bidirectional"))
      (node (ref "U10") (pin "3") (pinfunction "DI_3") (pintype "passive"))
    )
    (net (code "80") (name "Net-(U1-EESK)") (class "Default")
      (node (ref "U1") (pin "1") (pinfunction "EESK_1") (pintype "output"))
      (node (ref "U10") (pin "2") (pinfunction "CLK_2") (pintype "passive"))
    )
    (net (code "81") (name "Net-(U1-RESET#)") (class "Default")
      (node (ref "R10") (pin "1") (pinfunction "1_1") (pintype "passive"))
      (node (ref "R9") (pin "2") (pinfunction "2_2") (pintype "passive"))
      (node (ref "U1") (pin "4") (pinfunction "RESET#_4") (pintype "input"))
    )
    (net (code "82") (name "Net-(U1-RSTOUT#)") (class "Default")
      (node (ref "R8") (pin "1") (pinfunction "1_1") (pintype "passive"))
      (node (ref "U1") (pin "5") (pinfunction "RSTOUT#_5") (pintype "output"))
    )
    (net (code "83") (name "Net-(U1-USBDM)") (class "Default")
      (node (ref "R6") (pin "1") (pinfunction "1_1") (pintype "passive"))
      (node (ref "U1") (pin "8") (pinfunction "USBDM_8") (pintype "bidirectional"))
    )
    (net (code "84") (name "Net-(U1-USBDP)") (class "Default")
      (node (ref "R7") (pin "1") (pinfunction "1_1") (pintype "passive"))
      (node (ref "R8") (pin "2") (pinfunction "2_2") (pintype "passive"))
      (node (ref "U1") (pin "7") (pinfunction "USBDP_7") (pintype "bidirectional"))
    )
    (net (code "85") (name "Net-(U1-XTIN)") (class "Default")
      (node (ref "R15") (pin "2") (pinfunction "2_2") (pintype "passive"))
      (node (ref "U1") (pin "27") (pinfunction "XTIN_27") (pintype "input"))
      (node (ref "Y2") (pin "1") (pinfunction "1_1") (pintype "passive"))
    )
    (net (code "86") (name "Net-(U1-XTOUT)") (class "Default")
      (node (ref "R15") (pin "1") (pinfunction "1_1") (pintype "passive"))
      (node (ref "U1") (pin "28") (pinfunction "XTOUT_28") (pintype "output"))
      (node (ref "Y2") (pin "3") (pinfunction "3_3") (pintype "passive"))
    )
    (net (code "87") (name "Net-(U10-DO)") (class "Default")
      (node (ref "R16") (pin "1") (pinfunction "1_1") (pintype "passive"))
      (node (ref "R17") (pin "2") (pinfunction "2_2") (pintype "passive"))
      (node (ref "U10") (pin "4") (pinfunction "DO_4") (pintype "output"))
    )
    (net (code "88") (name "unconnected-(IC3-(A8)PC0-Pad53)") (class "Default")
      (node (ref "IC3") (pin "53") (pinfunction "(A8)PC0_53") (pintype "passive"))
    )
    (net (code "89") (name "unconnected-(IC3-(A9)PC1-Pad54)") (class "Default")
      (node (ref "IC3") (pin "54") (pinfunction "(A9)PC1_54") (pintype "passive"))
    )
    (net (code "90") (name "unconnected-(IC3-(A10)PC2-Pad55)") (class "Default")
      (node (ref "IC3") (pin "55") (pinfunction "(A10)PC2_55") (pintype "passive"))
    )
    (net (code "91") (name "unconnected-(IC3-(A11)PC3-Pad56)") (class "Default")
      (node (ref "IC3") (pin "56") (pinfunction "(A11)PC3_56") (pintype "passive"))
    )
    (net (code "92") (name "unconnected-(IC3-(A12)PC4-Pad57)") (class "Default")
      (node (ref "IC3") (pin "57") (pinfunction "(A12)PC4_57") (pintype "passive"))
    )
    (net (code "93") (name "unconnected-(IC3-(A13)PC5-Pad58)") (class "Default")
      (node (ref "IC3") (pin "58") (pinfunction "(A13)PC5_58") (pintype "passive"))
    )
    (net (code "94") (name "unconnected-(IC3-(A14)PC6-Pad59)") (class "Default")
      (node (ref "IC3") (pin "59") (pinfunction "(A14)PC6_59") (pintype "passive"))
    )
    (net (code "95") (name "unconnected-(IC3-(A15)PC7-Pad60)") (class "Default")
      (node (ref "IC3") (pin "60") (pinfunction "(A15)PC7_60") (pintype "passive"))
    )
    (net (code "96") (name "unconnected-(IC3-(AD0)PA0-Pad78)") (class "Default")
      (node (ref "IC3") (pin "78") (pinfunction "(AD0)PA0_78") (pintype "passive"))
    )
    (net (code "97") (name "unconnected-(IC3-(AD1)PA1-Pad77)") (class "Default")
      (node (ref "IC3") (pin "77") (pinfunction "(AD1)PA1_77") (pintype "passive"))
    )
    (net (code "98") (name "unconnected-(IC3-(AD2)PA2-Pad76)") (class "Default")
      (node (ref "IC3") (pin "76") (pinfunction "(AD2)PA2_76") (pintype "passive"))
    )
    (net (code "99") (name "unconnected-(IC3-(AD3)PA3-Pad75)") (class "Default")
      (node (ref "IC3") (pin "75") (pinfunction "(AD3)PA3_75") (pintype "passive"))
    )
    (net (code "100") (name "unconnected-(IC3-(AD4)PA4-Pad74)") (class "Default")
      (node (ref "IC3") (pin "74") (pinfunction "(AD4)PA4_74") (pintype "passive"))
    )
    (net (code "101") (name "unconnected-(IC3-(AD5)PA5-Pad73)") (class "Default")
      (node (ref "IC3") (pin "73") (pinfunction "(AD5)PA5_73") (pintype "passive"))
    )
    (net (code "102") (name "unconnected-(IC3-(AD6)PA6-Pad72)") (class "Default")
      (node (ref "IC3") (pin "72") (pinfunction "(AD6)PA6_72") (pintype "passive"))
    )
    (net (code "103") (name "unconnected-(IC3-(AD7)PA7-Pad71)") (class "Default")
      (node (ref "IC3") (pin "71") (pinfunction "(AD7)PA7_71") (pintype "passive"))
    )
    (net (code "104") (name "unconnected-(IC3-(ADC0)PF0-Pad97)") (class "Default")
      (node (ref "IC3") (pin "97") (pinfunction "(ADC0)PF0_97") (pintype "passive"))
    )
    (net (code "105") (name "unconnected-(IC3-(ADC1)PF1-Pad96)") (class "Default")
      (node (ref "IC3") (pin "96") (pinfunction "(ADC1)PF1_96") (pintype "passive"))
    )
    (net (code "106") (name "unconnected-(IC3-(ADC2)PF2-Pad95)") (class "Default")
      (node (ref "IC3") (pin "95") (pinfunction "(ADC2)PF2_95") (pintype "passive"))
    )
    (net (code "107") (name "unconnected-(IC3-(ADC3)PF3-Pad94)") (class "Default")
      (node (ref "IC3") (pin "94") (pinfunction "(ADC3)PF3_94") (pintype "passive"))
    )
    (net (code "108") (name "unconnected-(IC3-(ADC4{slash}TCK)PF4-Pad93)") (class "Default")
      (node (ref "IC3") (pin "93") (pinfunction "(ADC4/TCK)PF4_93") (pintype "passive"))
    )
    (net (code "109") (name "unconnected-(IC3-(ADC5{slash}TMS)PF5-Pad92)") (class "Default")
      (node (ref "IC3") (pin "92") (pinfunction "(ADC5/TMS)PF5_92") (pintype "passive"))
    )
    (net (code "110") (name "unconnected-(IC3-(ADC6{slash}TDO)PF6-Pad91)") (class "Default")
      (node (ref "IC3") (pin "91") (pinfunction "(ADC6/TDO)PF6_91") (pintype "passive"))
    )
    (net (code "111") (name "unconnected-(IC3-(ADC7{slash}TDI)PF7-Pad90)") (class "Default")
      (node (ref "IC3") (pin "90") (pinfunction "(ADC7/TDI)PF7_90") (pintype "passive"))
    )
    (net (code "112") (name "unconnected-(IC3-(ALE)PG2-Pad70)") (class "Default")
      (node (ref "IC3") (pin "70") (pinfunction "(ALE)PG2_70") (pintype "passive"))
    )
    (net (code "113") (name "unconnected-(IC3-(CLKO{slash}ICP3{slash}INT7)PE7-Pad9)") (class "Default")
      (node (ref "IC3") (pin "9") (pinfunction "(CLKO/ICP3/INT7)PE7_9") (pintype "passive"))
    )
    (net (code "114") (name "unconnected-(IC3-(ICP1)PD4-Pad47)") (class "Default")
      (node (ref "IC3") (pin "47") (pinfunction "(ICP1)PD4_47") (pintype "passive"))
    )
    (net (code "115") (name "unconnected-(IC3-(OC0A{slash}OC1C{slash}PCINT7)PB7-Pad26)") (class "Default")
      (node (ref "IC3") (pin "26") (pinfunction "(OC0A/OC1C/PCINT7)PB7_26") (pintype "passive"))
    )
    (net (code "116") (name "unconnected-(IC3-(OC0B)PG5-Pad1)") (class "Default")
      (node (ref "IC3") (pin "1") (pinfunction "(OC0B)PG5_1") (pintype "passive"))
    )
    (net (code "117") (name "unconnected-(IC3-(OC1A{slash}PCINT5)PB5-Pad24)") (class "Default")
      (node (ref "IC3") (pin "24") (pinfunction "(OC1A/PCINT5)PB5_24") (pintype "passive"))
    )
    (net (code "118") (name "unconnected-(IC3-(OC1B{slash}PCINT6)PB6-Pad25)") (class "Default")
      (node (ref "IC3") (pin "25") (pinfunction "(OC1B/PCINT6)PB6_25") (pintype "passive"))
    )
    (net (code "119") (name "unconnected-(IC3-(OC2A{slash}PCINT4)PB4-Pad23)") (class "Default")
      (node (ref "IC3") (pin "23") (pinfunction "(OC2A/PCINT4)PB4_23") (pintype "passive"))
    )
    (net (code "120") (name "unconnected-(IC3-(OC3A{slash}AIN1)PE3-Pad5)") (class "Default")
      (node (ref "IC3") (pin "5") (pinfunction "(OC3A/AIN1)PE3_5") (pintype "passive"))
    )
    (net (code "121") (name "unconnected-(IC3-(OC3B{slash}INT4)PE4-Pad6)") (class "Default")
      (node (ref "IC3") (pin "6") (pinfunction "(OC3B/INT4)PE4_6") (pintype "passive"))
    )
    (net (code "122") (name "unconnected-(IC3-(OC3C{slash}INT5)PE5-Pad7)") (class "Default")
      (node (ref "IC3") (pin "7") (pinfunction "(OC3C/INT5)PE5_7") (pintype "passive"))
    )
    (net (code "123") (name "unconnected-(IC3-(RD)PG1-Pad52)") (class "Default")
      (node (ref "IC3") (pin "52") (pinfunction "(RD)PG1_52") (pintype "passive"))
    )
    (net (code "124") (name "unconnected-(IC3-(SS{slash}PCINT0)PB0-Pad19)") (class "Default")
      (node (ref "IC3") (pin "19") (pinfunction "(SS/PCINT0)PB0_19") (pintype "passive"))
    )
    (net (code "125") (name "unconnected-(IC3-(T0)PD7-Pad50)") (class "Default")
      (node (ref "IC3") (pin "50") (pinfunction "(T0)PD7_50") (pintype "passive"))
    )
    (net (code "126") (name "unconnected-(IC3-(T1)PD6-Pad49)") (class "Default")
      (node (ref "IC3") (pin "49") (pinfunction "(T1)PD6_49") (pintype "passive"))
    )
    (net (code "127") (name "unconnected-(IC3-(T3{slash}INT6)PE6-Pad8)") (class "Default")
      (node (ref "IC3") (pin "8") (pinfunction "(T3/INT6)PE6_8") (pintype "passive"))
    )
    (net (code "128") (name "unconnected-(IC3-(TOSC1)PG4-Pad29)") (class "Default")
      (node (ref "IC3") (pin "29") (pinfunction "(TOSC1)PG4_29") (pintype "passive"))
    )
    (net (code "129") (name "unconnected-(IC3-(TOSC2)PG3-Pad28)") (class "Default")
      (node (ref "IC3") (pin "28") (pinfunction "(TOSC2)PG3_28") (pintype "passive"))
    )
    (net (code "130") (name "unconnected-(IC3-(WR)PG0-Pad51)") (class "Default")
      (node (ref "IC3") (pin "51") (pinfunction "(WR)PG0_51") (pintype "passive"))
    )
    (net (code "131") (name "unconnected-(IC3-(XCK0{slash}AIN0)PE2-Pad4)") (class "Default")
      (node (ref "IC3") (pin "4") (pinfunction "(XCK0/AIN0)PE2_4") (pintype "passive"))
    )
    (net (code "132") (name "unconnected-(IC3-(XCK1)PD5-Pad48)") (class "Default")
      (node (ref "IC3") (pin "48") (pinfunction "(XCK1)PD5_48") (pintype "passive"))
    )
    (net (code "133") (name "unconnected-(IC3-PH0(RXD2)-Pad12)") (class "Default")
      (node (ref "IC3") (pin "12") (pinfunction "PH0(RXD2)_12") (pintype "passive"))
    )
    (net (code "134") (name "unconnected-(IC3-PH1(TXD2)-Pad13)") (class "Default")
      (node (ref "IC3") (pin "13") (pinfunction "PH1(TXD2)_13") (pintype "passive"))
    )
    (net (code "135") (name "unconnected-(IC3-PH2(XCK2)-Pad14)") (class "Default")
      (node (ref "IC3") (pin "14") (pinfunction "PH2(XCK2)_14") (pintype "passive"))
    )
    (net (code "136") (name "unconnected-(IC3-PH3(OC4A)-Pad15)") (class "Default")
      (node (ref "IC3") (pin "15") (pinfunction "PH3(OC4A)_15") (pintype "passive"))
    )
    (net (code "137") (name "unconnected-(IC3-PH4(OC4B)-Pad16)") (class "Default")
      (node (ref "IC3") (pin "16") (pinfunction "PH4(OC4B)_16") (pintype "passive"))
    )
    (net (code "138") (name "unconnected-(IC3-PH5(OC4C)-Pad17)") (class "Default")
      (node (ref "IC3") (pin "17") (pinfunction "PH5(OC4C)_17") (pintype "passive"))
    )
    (net (code "139") (name "unconnected-(IC3-PH6(OC2B)-Pad18)") (class "Default")
      (node (ref "IC3") (pin "18") (pinfunction "PH6(OC2B)_18") (pintype "passive"))
    )
    (net (code "140") (name "unconnected-(IC3-PH7(T4)-Pad27)") (class "Default")
      (node (ref "IC3") (pin "27") (pinfunction "PH7(T4)_27") (pintype "passive"))
    )
    (net (code "141") (name "unconnected-(IC3-PJ0(RXD3{slash}PCINT9)-Pad63)") (class "Default")
      (node (ref "IC3") (pin "63") (pinfunction "PJ0(RXD3/PCINT9)_63") (pintype "passive"))
    )
    (net (code "142") (name "unconnected-(IC3-PJ1(TXD3{slash}PCINT10)-Pad64)") (class "Default")
      (node (ref "IC3") (pin "64") (pinfunction "PJ1(TXD3/PCINT10)_64") (pintype "passive"))
    )
    (net (code "143") (name "unconnected-(IC3-PJ2(XCK3{slash}PCINT11)-Pad65)") (class "Default")
      (node (ref "IC3") (pin "65") (pinfunction "PJ2(XCK3/PCINT11)_65") (pintype "passive"))
    )
    (net (code "144") (name "unconnected-(IC3-PJ3(PCINT12)-Pad66)") (class "Default")
      (node (ref "IC3") (pin "66") (pinfunction "PJ3(PCINT12)_66") (pintype "passive"))
    )
    (net (code "145") (name "unconnected-(IC3-PJ4(PCINT13)-Pad67)") (class "Default")
      (node (ref "IC3") (pin "67") (pinfunction "PJ4(PCINT13)_67") (pintype "passive"))
    )
    (net (code "146") (name "unconnected-(IC3-PJ5(PCINT14)-Pad68)") (class "Default")
      (node (ref "IC3") (pin "68") (pinfunction "PJ5(PCINT14)_68") (pintype "passive"))
    )
    (net (code "147") (name "unconnected-(IC3-PJ6(PCINT15)-Pad69)") (class "Default")
      (node (ref "IC3") (pin "69") (pinfunction "PJ6(PCINT15)_69") (pintype "passive"))
    )
    (net (code "148") (name "unconnected-(IC3-PJ7-Pad79)") (class "Default")
      (node (ref "IC3") (pin "79") (pinfunction "PJ7_79") (pintype "passive"))
    )
    (net (code "149") (name "unconnected-(IC3-PK0(ADC8{slash}PCINT16)-Pad89)") (class "Default")
      (node (ref "IC3") (pin "89") (pinfunction "PK0(ADC8/PCINT16)_89") (pintype "passive"))
    )
    (net (code "150") (name "unconnected-(IC3-PK1(ADC9{slash}PCINT17)-Pad88)") (class "Default")
      (node (ref "IC3") (pin "88") (pinfunction "PK1(ADC9/PCINT17)_88") (pintype "passive"))
    )
    (net (code "151") (name "unconnected-(IC3-PK2(ADC10{slash}PCINT18)-Pad87)") (class "Default")
      (node (ref "IC3") (pin "87") (pinfunction "PK2(ADC10/PCINT18)_87") (pintype "passive"))
    )
    (net (code "152") (name "unconnected-(IC3-PK3(ADC11{slash}PCINT19)-Pad86)") (class "Default")
      (node (ref "IC3") (pin "86") (pinfunction "PK3(ADC11/PCINT19)_86") (pintype "passive"))
    )
    (net (code "153") (name "unconnected-(IC3-PK4(ADC12{slash}PCINT20)-Pad85)") (class "Default")
      (node (ref "IC3") (pin "85") (pinfunction "PK4(ADC12/PCINT20)_85") (pintype "passive"))
    )
    (net (code "154") (name "unconnected-(IC3-PK5(ADC13{slash}PCINT21)-Pad84)") (class "Default")
      (node (ref "IC3") (pin "84") (pinfunction "PK5(ADC13/PCINT21)_84") (pintype "passive"))
    )
    (net (code "155") (name "unconnected-(IC3-PK6(ADC14{slash}PCINT22)-Pad83)") (class "Default")
      (node (ref "IC3") (pin "83") (pinfunction "PK6(ADC14/PCINT22)_83") (pintype "passive"))
    )
    (net (code "156") (name "unconnected-(IC3-PK7(ADC15{slash}PCINT23)-Pad82)") (class "Default")
      (node (ref "IC3") (pin "82") (pinfunction "PK7(ADC15/PCINT23)_82") (pintype "passive"))
    )
    (net (code "157") (name "unconnected-(IC3-PL3(OC5A)-Pad38)") (class "Default")
      (node (ref "IC3") (pin "38") (pinfunction "PL3(OC5A)_38") (pintype "passive"))
    )
    (net (code "158") (name "unconnected-(ICSP1-Pad3)") (class "Default")
      (node (ref "ICSP1") (pin "3") (pinfunction "3_3") (pintype "passive"))
    )
    (net (code "159") (name "unconnected-(P1-SENSE+-Pad7)") (class "Default")
      (node (ref "P1") (pin "7") (pinfunction "SENSE+_7") (pintype "passive"))
    )
    (net (code "160") (name "unconnected-(P1-SENSE--Pad5)") (class "Default")
      (node (ref "P1") (pin "5") (pinfunction "SENSE-_5") (pintype "passive"))
    )
    (net (code "161") (name "unconnected-(U1-DCD#-Pad19)") (class "Default")
      (node (ref "U1") (pin "19") (pinfunction "DCD#_19") (pintype "input"))
    )
    (net (code "162") (name "unconnected-(U1-DSR#-Pad20)") (class "Default")
      (node (ref "U1") (pin "20") (pinfunction "DSR#_20") (pintype "input"))
    )
    (net (code "163") (name "unconnected-(U1-PWREN#-Pad15)") (class "Default")
      (node (ref "U1") (pin "15") (pinfunction "PWREN#_15") (pintype "output"))
    )
    (net (code "164") (name "unconnected-(U1-RI#-Pad18)") (class "Default")
      (node (ref "U1") (pin "18") (pinfunction "RI#_18") (pintype "input"))
    )
    (net (code "165") (name "unconnected-(U1-RTS#-Pad23)") (class "Default")
      (node (ref "U1") (pin "23") (pinfunction "RTS#_23") (pintype "output"))
    )
    (net (code "166") (name "unconnected-(U1-SLEEP#-Pad10)") (class "Default")
      (node (ref "U1") (pin "10") (pinfunction "SLEEP#_10") (pintype "output"))
    )
    (net (code "167") (name "unconnected-(U1-TXDEN-Pad16)") (class "Default")
      (node (ref "U1") (pin "16") (pinfunction "TXDEN_16") (pintype "output"))
    )
    (net (code "168") (name "unconnected-(U10-NC-Pad7)") (class "Default")
      (node (ref "U10") (pin "7") (pinfunction "NC_7") (pintype "passive"))
    )
    (net (code "169") (name "unconnected-(U10-NC_2-Pad6)") (class "Default")
      (node (ref "U10") (pin "6") (pinfunction "NC_2_6") (pintype "passive"))
    )
  )
)
